# Display.net
KiCad netlist of a schematic drawn in Altium Designer
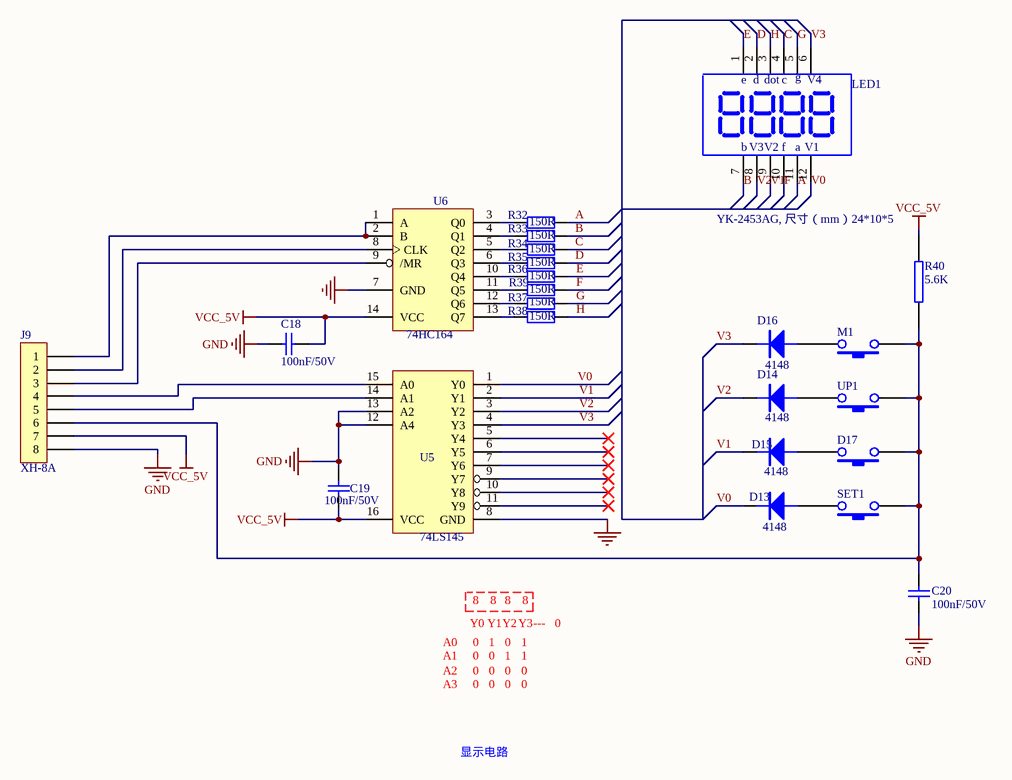
[diagram p0: Display.SchDoc]

(export (version "E")
  (design (tool "Eeschema 10.0.6"))
  (components
    (comp (ref "C18")
      (value "100nF/50V")
      (footprint "0603C")
      (description "瓷片电容,100nF,5%,X7R,50V,0603")
      (libsource (lib "SR SCH Library V02") (part "C100nF/50V-0603"))
    )
    (comp (ref "C19")
      (value "100nF/50V")
      (footprint "0603C")
      (description "瓷片电容,100nF,5%,X7R,50V,0603")
      (libsource (lib "SR SCH Library V02") (part "C100nF/50V-0603"))
    )
    (comp (ref "C20")
      (value "100nF/50V")
      (footprint "0603C")
      (description "瓷片电容,100nF,5%,X7R,50V,0603")
      (libsource (lib "SR SCH Library V02") (part "C100nF/50V-0603"))
    )
    (comp (ref "D13")
      (value "4148")
      (footprint "LL-34")
      (description "Diode")
      (libsource (lib "*") (part "DIODE"))
    )
    (comp (ref "D14")
      (value "4148")
      (footprint "LL-34")
      (description "Diode")
      (libsource (lib "*") (part "DIODE"))
    )
    (comp (ref "D15")
      (value "4148")
      (footprint "LL-34")
      (description "Diode")
      (libsource (lib "*") (part "DIODE"))
    )
    (comp (ref "D16")
      (value "4148")
      (footprint "LL-34")
      (description "Diode")
      (libsource (lib "*") (part "DIODE"))
    )
    (comp (ref "D17") (value "~") (footprint "SW6545") (libsource (lib "*") (part "SW-PB")))
    (comp (ref "J9")
      (value "XH-8A")
      (footprint "PH2.0MM-8PIN")
      (description "CONN,XH-8A,8PIN,2.54mm插座")
      (libsource (lib "SR SCH Library V02") (part "CONN-XH-8A"))
    )
    (comp (ref "LED1")
      (value "YK-2453AG, 尺寸（mm）24*10*5")
      (footprint "DigitalTube_4W")
      (description "数码管，红色，共阴，尺寸（mm）24*10*5")
      (libsource (lib "Next_SCHlib") (part "数码管，红色，共阴，尺寸（mm）24*10*5"))
    )
    (comp (ref "M1") (value "~") (footprint "SW6545") (libsource (lib "*") (part "SW-PB")))
    (comp (ref "R32")
      (value "150R")
      (footprint "0805R")
      (description "金属膜电阻,150R,1%,1/8W,0805")
      (libsource (lib "SR SCH Library V02") (part "R150R-0805"))
    )
    (comp (ref "R33")
      (value "150R")
      (footprint "0805R")
      (description "金属膜电阻,150R,1%,1/8W,0805")
      (libsource (lib "SR SCH Library V02") (part "R150R-0805"))
    )
    (comp (ref "R34")
      (value "150R")
      (footprint "0805R")
      (description "金属膜电阻,150R,1%,1/8W,0805")
      (libsource (lib "SR SCH Library V02") (part "R150R-0805"))
    )
    (comp (ref "R35")
      (value "150R")
      (footprint "0805R")
      (description "金属膜电阻,150R,1%,1/8W,0805")
      (libsource (lib "SR SCH Library V02") (part "R150R-0805"))
    )
    (comp (ref "R36")
      (value "150R")
      (footprint "0805R")
      (description "金属膜电阻,150R,1%,1/8W,0805")
      (libsource (lib "SR SCH Library V02") (part "R150R-0805"))
    )
    (comp (ref "R37")
      (value "150R")
      (footprint "0805R")
      (description "金属膜电阻,150R,1%,1/8W,0805")
      (libsource (lib "SR SCH Library V02") (part "R150R-0805"))
    )
    (comp (ref "R38")
      (value "150R")
      (footprint "0805R")
      (description "金属膜电阻,150R,1%,1/8W,0805")
      (libsource (lib "SR SCH Library V02") (part "R150R-0805"))
    )
    (comp (ref "R39")
      (value "150R")
      (footprint "0805R")
      (description "金属膜电阻,150R,1%,1/8W,0805")
      (libsource (lib "SR SCH Library V02") (part "R150R-0805"))
    )
    (comp (ref "R40") (value "5.6K") (footprint "0603R") (libsource (lib "*") (part "RES2")))
    (comp (ref "SET1") (value "~") (footprint "SW6545") (libsource (lib "*") (part "SW-PB")))
    (comp (ref "U5") (value "74LS145") (footprint "SO-16") (libsource (lib "*") (part "74LS595")))
    (comp (ref "U6")
      (value "74HC164")
      (footprint "SO-14")
      (description "74LS164")
      (libsource (lib "*") (part "74LS164"))
    )
    (comp (ref "UP1") (value "~") (footprint "SW6545") (libsource (lib "*") (part "SW-PB")))
  )
  (nets
    (net (code "1") (name "/A") (class "Default")
      (node (ref "LED1") (pin "11") (pinfunction "11_11") (pintype "passive"))
      (node (ref "R32") (pin "2") (pinfunction "2_2") (pintype "passive"))
    )
    (net (code "2") (name "/B") (class "Default")
      (node (ref "LED1") (pin "7") (pinfunction "B_7") (pintype "passive"))
      (node (ref "R33") (pin "2") (pinfunction "2_2") (pintype "passive"))
    )
    (net (code "3") (name "/C") (class "Default")
      (node (ref "LED1") (pin "4") (pinfunction "4_4") (pintype "passive"))
      (node (ref "R34") (pin "2") (pinfunction "2_2") (pintype "passive"))
    )
    (net (code "4") (name "/D") (class "Default")
      (node (ref "LED1") (pin "2") (pinfunction "2_2") (pintype "passive"))
      (node (ref "R35") (pin "2") (pinfunction "2_2") (pintype "passive"))
    )
    (net (code "5") (name "/E") (class "Default")
      (node (ref "LED1") (pin "1") (pinfunction "1_1") (pintype "passive"))
      (node (ref "R36") (pin "2") (pinfunction "2_2") (pintype "passive"))
    )
    (net (code "6") (name "/F") (class "Default")
      (node (ref "LED1") (pin "10") (pinfunction "10_10") (pintype "passive"))
      (node (ref "R39") (pin "2") (pinfunction "2_2") (pintype "passive"))
    )
    (net (code "7") (name "/G") (class "Default")
      (node (ref "LED1") (pin "5") (pinfunction "5_5") (pintype "passive"))
      (node (ref "R37") (pin "2") (pinfunction "2_2") (pintype "passive"))
    )
    (net (code "8") (name "/H") (class "Default")
      (node (ref "LED1") (pin "3") (pinfunction "3_3") (pintype "passive"))
      (node (ref "R38") (pin "2") (pinfunction "2_2") (pintype "passive"))
    )
    (net (code "9") (name "/V0") (class "Default")
      (node (ref "D13") (pin "2") (pinfunction "K_2") (pintype "passive"))
      (node (ref "LED1") (pin "12") (pinfunction "12_12") (pintype "passive"))
      (node (ref "U5") (pin "1") (pinfunction "Y0_1") (pintype "passive"))
    )
    (net (code "10") (name "/V1") (class "Default")
      (node (ref "D15") (pin "2") (pinfunction "K_2") (pintype "passive"))
      (node (ref "LED1") (pin "9") (pinfunction "9_9") (pintype "passive"))
      (node (ref "U5") (pin "2") (pinfunction "Y1_2") (pintype "passive"))
    )
    (net (code "11") (name "/V2") (class "Default")
      (node (ref "D14") (pin "2") (pinfunction "K_2") (pintype "passive"))
      (node (ref "LED1") (pin "8") (pinfunction "8_8") (pintype "passive"))
      (node (ref "U5") (pin "3") (pinfunction "Y2_3") (pintype "passive"))
    )
    (net (code "12") (name "/V3") (class "Default")
      (node (ref "D16") (pin "2") (pinfunction "K_2") (pintype "passive"))
      (node (ref "LED1") (pin "6") (pinfunction "6_6") (pintype "passive"))
      (node (ref "U5") (pin "4") (pinfunction "Y3_4") (pintype "passive"))
    )
    (net (code "13") (name "GND") (class "Default")
      (node (ref "C18") (pin "2") (pinfunction "2_2") (pintype "passive"))
      (node (ref "C19") (pin "2") (pinfunction "2_2") (pintype "passive"))
      (node (ref "C20") (pin "1") (pinfunction "1_1") (pintype "passive"))
      (node (ref "J9") (pin "8") (pinfunction "8_8") (pintype "passive"))
      (node (ref "U5") (pin "12") (pinfunction "A4_12") (pintype "passive"))
      (node (ref "U5") (pin "13") (pinfunction "A2_13") (pintype "passive"))
      (node (ref "U5") (pin "8") (pinfunction "GND_8") (pintype "passive"))
      (node (ref "U6") (pin "7") (pinfunction "GND_7") (pintype "passive"))
    )
    (net (code "14") (name "Net-(C20-Pad2)") (class "Default")
      (node (ref "C20") (pin "2") (pinfunction "2_2") (pintype "passive"))
      (node (ref "D17") (pin "1") (pinfunction "1_1") (pintype "passive"))
      (node (ref "J9") (pin "6") (pinfunction "6_6") (pintype "passive"))
      (node (ref "M1") (pin "1") (pinfunction "1_1") (pintype "passive"))
      (node (ref "R40") (pin "1") (pinfunction "1_1") (pintype "passive"))
      (node (ref "SET1") (pin "1") (pinfunction "1_1") (pintype "passive"))
      (node (ref "UP1") (pin "1") (pinfunction "1_1") (pintype "passive"))
    )
    (net (code "15") (name "Net-(D13-A)") (class "Default")
      (node (ref "D13") (pin "1") (pinfunction "A_1") (pintype "passive"))
      (node (ref "SET1") (pin "2") (pinfunction "2_2") (pintype "passive"))
    )
    (net (code "16") (name "Net-(D14-A)") (class "Default")
      (node (ref "D14") (pin "1") (pinfunction "A_1") (pintype "passive"))
      (node (ref "UP1") (pin "2") (pinfunction "2_2") (pintype "passive"))
    )
    (net (code "17") (name "Net-(D15-A)") (class "Default")
      (node (ref "D15") (pin "1") (pinfunction "A_1") (pintype "passive"))
      (node (ref "D17") (pin "2") (pinfunction "2_2") (pintype "passive"))
    )
    (net (code "18") (name "Net-(D16-A)") (class "Default")
      (node (ref "D16") (pin "1") (pinfunction "A_1") (pintype "passive"))
      (node (ref "M1") (pin "2") (pinfunction "2_2") (pintype "passive"))
    )
    (net (code "19") (name "Net-(U5-A0)") (class "Default")
      (node (ref "J9") (pin "4") (pinfunction "4_4") (pintype "passive"))
      (node (ref "U5") (pin "15") (pinfunction "A0_15") (pintype "passive"))
    )
    (net (code "20") (name "Net-(U5-A1)") (class "Default")
      (node (ref "J9") (pin "5") (pinfunction "5_5") (pintype "passive"))
      (node (ref "U5") (pin "14") (pinfunction "A1_14") (pintype "passive"))
    )
    (net (code "21") (name "Net-(U6-A)") (class "Default")
      (node (ref "J9") (pin "1") (pinfunction "1_1") (pintype "passive"))
      (node (ref "U6") (pin "1") (pinfunction "A_1") (pintype "passive"))
      (node (ref "U6") (pin "2") (pinfunction "B_2") (pintype "passive"))
    )
    (net (code "22") (name "Net-(U6-CLK)") (class "Default")
      (node (ref "J9") (pin "2") (pinfunction "2_2") (pintype "passive"))
      (node (ref "U6") (pin "8") (pinfunction "CLK_8") (pintype "passive"))
    )
    (net (code "23") (name "Net-(U6-Q0)") (class "Default")
      (node (ref "R32") (pin "1") (pinfunction "1_1") (pintype "passive"))
      (node (ref "U6") (pin "3") (pinfunction "Q0_3") (pintype "passive"))
    )
    (net (code "24") (name "Net-(U6-Q1)") (class "Default")
      (node (ref "R33") (pin "1") (pinfunction "1_1") (pintype "passive"))
      (node (ref "U6") (pin "4") (pinfunction "Q1_4") (pintype "passive"))
    )
    (net (code "25") (name "Net-(U6-Q2)") (class "Default")
      (node (ref "R34") (pin "1") (pinfunction "1_1") (pintype "passive"))
      (node (ref "U6") (pin "5") (pinfunction "Q2_5") (pintype "passive"))
    )
    (net (code "26") (name "Net-(U6-Q3)") (class "Default")
      (node (ref "R35") (pin "1") (pinfunction "1_1") (pintype "passive"))
      (node (ref "U6") (pin "6") (pinfunction "Q3_6") (pintype "passive"))
    )
    (net (code "27") (name "Net-(U6-Q4)") (class "Default")
      (node (ref "R36") (pin "1") (pinfunction "1_1") (pintype "passive"))
      (node (ref "U6") (pin "10") (pinfunction "Q4_10") (pintype "passive"))
    )
    (net (code "28") (name "Net-(U6-Q5)") (class "Default")
      (node (ref "R39") (pin "1") (pinfunction "1_1") (pintype "passive"))
      (node (ref "U6") (pin "11") (pinfunction "Q5_11") (pintype "passive"))
    )
    (net (code "29") (name "Net-(U6-Q6)") (class "Default")
      (node (ref "R37") (pin "1") (pinfunction "1_1") (pintype "passive"))
      (node (ref "U6") (pin "12") (pinfunction "Q6_12") (pintype "passive"))
    )
    (net (code "30") (name "Net-(U6-Q7)") (class "Default")
      (node (ref "R38") (pin "1") (pinfunction "1_1") (pintype "passive"))
      (node (ref "U6") (pin "13") (pinfunction "Q7_13") (pintype "passive"))
    )
    (net (code "31") (name "Net-(U6-{slash}MR)") (class "Default")
      (node (ref "J9") (pin "3") (pinfunction "3_3") (pintype "passive"))
      (node (ref "U6") (pin "9") (pinfunction "/MR_9") (pintype "passive"))
    )
    (net (code "32") (name "VCC_5V") (class "Default")
      (node (ref "C18") (pin "1") (pinfunction "1_1") (pintype "passive"))
      (node (ref "C19") (pin "1") (pinfunction "1_1") (pintype "passive"))
      (node (ref "J9") (pin "7") (pinfunction "7_7") (pintype "passive"))
      (node (ref "R40") (pin "2") (pinfunction "2_2") (pintype "passive"))
      (node (ref "U5") (pin "16") (pinfunction "VCC_16") (pintype "passive"))
      (node (ref "U6") (pin "14") (pinfunction "VCC_14") (pintype "passive"))
    )
    (net (code "33") (name "unconnected-(U5-Y4-Pad5)") (class "Default")
      (node (ref "U5") (pin "5") (pinfunction "Y4_5") (pintype "passive+no_connect"))
    )
    (net (code "34") (name "unconnected-(U5-Y5-Pad6)") (class "Default")
      (node (ref "U5") (pin "6") (pinfunction "Y5_6") (pintype "passive+no_connect"))
    )
    (net (code "35") (name "unconnected-(U5-Y6-Pad7)") (class "Default")
      (node (ref "U5") (pin "7") (pinfunction "Y6_7") (pintype "passive+no_connect"))
    )
    (net (code "36") (name "unconnected-(U5-Y7-Pad9)") (class "Default")
      (node (ref "U5") (pin "9") (pinfunction "Y7_9") (pintype "passive+no_connect"))
    )
    (net (code "37") (name "unconnected-(U5-Y8-Pad10)") (class "Default")
      (node (ref "U5") (pin "10") (pinfunction "Y8_10") (pintype "passive+no_connect"))
    )
    (net (code "38") (name "unconnected-(U5-Y9-Pad11)") (class "Default")
      (node (ref "U5") (pin "11") (pinfunction "Y9_11") (pintype "passive+no_connect"))
    )
  )
)
